# wifi_main_fix.net
KiCad netlist of a schematic drawn in EAGLE
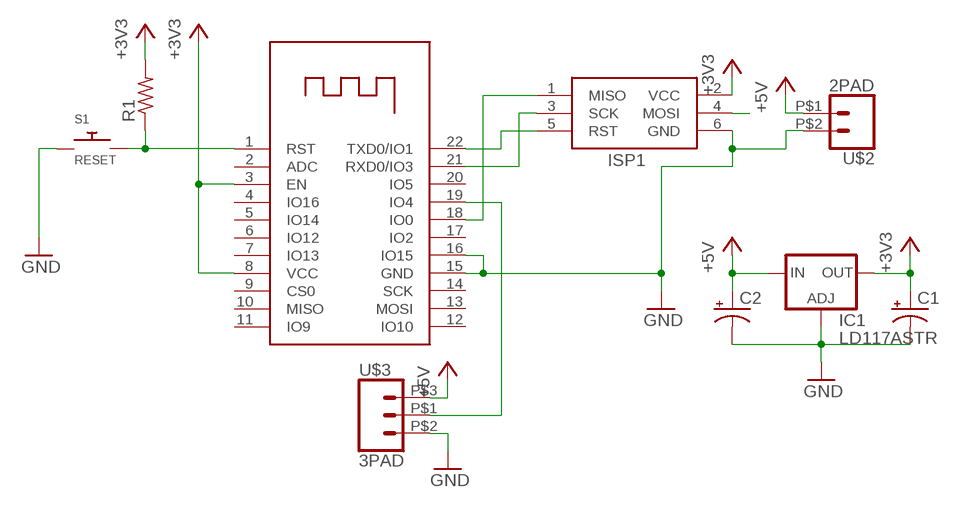
[diagram p0: schematic, sheet 1]

(export (version "E")
  (design (tool "Eeschema 10.0.6"))
  (components
    (comp (ref "C1")
      (value "CPOL-US153CLV-0405")
      (footprint "eagle-import:153CLV-0405")
      (libsource (lib "eagle-import") (part "CPOL-US153CLV-0405"))
    )
    (comp (ref "C2")
      (value "CPOL-US153CLV-0405")
      (footprint "eagle-import:153CLV-0405")
      (libsource (lib "eagle-import") (part "CPOL-US153CLV-0405"))
    )
    (comp (ref "IC1")
      (value "LD117ASTR")
      (footprint "eagle-import:SOT223")
      (libsource (lib "eagle-import") (part "LD117A?STR"))
    )
    (comp (ref "ISP1")
      (value "AVRISP-6")
      (footprint "eagle-import:AVRISP")
      (libsource (lib "eagle-import") (part "AVRISP-6"))
    )
    (comp (ref "R1")
      (value "R-US_R0805")
      (footprint "eagle-import:R0805")
      (libsource (lib "eagle-import") (part "R-US_R0805"))
    )
    (comp (ref "S1")
      (value "RESET")
      (footprint "eagle-import:B3F-1000")
      (libsource (lib "eagle-import") (part "BUTTON"))
    )
    (comp (ref "U$1")
      (value "ESP-12F")
      (footprint "eagle-import:ESP-12F")
      (libsource (lib "eagle-import") (part "ESP-12F"))
    )
    (comp (ref "U$2")
      (value "2PAD")
      (footprint "eagle-import:2PAD")
      (libsource (lib "eagle-import") (part "2PAD"))
    )
    (comp (ref "U$3")
      (value "3PAD")
      (footprint "eagle-import:3PAD")
      (libsource (lib "eagle-import") (part "3PAD"))
    )
  )
  (nets
    (net (code "1") (name "+3V3") (class "Default")
      (node (ref "C1") (pin "+") (pinfunction "+_+") (pintype "passive"))
      (node (ref "IC1") (pin "4") (pinfunction "OUT_4") (pintype "passive"))
      (node (ref "ISP1") (pin "2") (pinfunction "VCC_2") (pintype "power_in"))
      (node (ref "R1") (pin "2") (pinfunction "2_2") (pintype "passive"))
      (node (ref "U$1") (pin "3") (pinfunction "EN_3") (pintype "bidirectional"))
      (node (ref "U$1") (pin "8") (pinfunction "VCC_8") (pintype "bidirectional"))
    )
    (net (code "2") (name "+5V") (class "Default")
      (node (ref "C2") (pin "+") (pinfunction "+_+") (pintype "passive"))
      (node (ref "IC1") (pin "3") (pinfunction "IN_3") (pintype "input"))
      (node (ref "U$2") (pin "P$1") (pinfunction "1_P$1") (pintype "passive"))
      (node (ref "U$3") (pin "P$3") (pinfunction "3_P$3") (pintype "passive"))
    )
    (net (code "3") (name "GND") (class "Default")
      (node (ref "C1") (pin "-") (pinfunction "-_-") (pintype "passive"))
      (node (ref "C2") (pin "-") (pinfunction "-_-") (pintype "passive"))
      (node (ref "IC1") (pin "1") (pinfunction "ADJ_1") (pintype "input"))
      (node (ref "ISP1") (pin "6") (pinfunction "GND_6") (pintype "power_in"))
      (node (ref "S1") (pin "1") (pinfunction "P$1_1") (pintype "passive"))
      (node (ref "S1") (pin "2") (pinfunction "P$1_2") (pintype "passive"))
      (node (ref "U$1") (pin "15") (pinfunction "GND_15") (pintype "bidirectional"))
      (node (ref "U$1") (pin "16") (pinfunction "IO15_16") (pintype "bidirectional"))
      (node (ref "U$2") (pin "P$2") (pinfunction "2_P$2") (pintype "passive"))
      (node (ref "U$3") (pin "P$2") (pinfunction "1_P$2") (pintype "passive"))
    )
    (net (code "4") (name "Net-(ISP1-MISO)") (class "Default")
      (node (ref "ISP1") (pin "1") (pinfunction "MISO_1") (pintype "input"))
      (node (ref "U$1") (pin "18") (pinfunction "IO0_18") (pintype "bidirectional"))
    )
    (net (code "5") (name "Net-(ISP1-RST)") (class "Default")
      (node (ref "ISP1") (pin "5") (pinfunction "RST_5") (pintype "output"))
      (node (ref "U$1") (pin "22") (pinfunction "TXD0/IO1_22") (pintype "bidirectional"))
    )
    (net (code "6") (name "Net-(ISP1-SCK)") (class "Default")
      (node (ref "ISP1") (pin "3") (pinfunction "SCK_3") (pintype "output"))
      (node (ref "U$1") (pin "21") (pinfunction "RXD0/IO3_21") (pintype "bidirectional"))
    )
    (net (code "7") (name "Net-(U$1-IO4)") (class "Default")
      (node (ref "U$1") (pin "19") (pinfunction "IO4_19") (pintype "bidirectional"))
      (node (ref "U$3") (pin "P$1") (pinfunction "2_P$1") (pintype "passive"))
    )
    (net (code "8") (name "Net-(U$1-RST)") (class "Default")
      (node (ref "R1") (pin "1") (pinfunction "1_1") (pintype "passive"))
      (node (ref "S1") (pin "3") (pinfunction "P$2_3") (pintype "passive"))
      (node (ref "S1") (pin "4") (pinfunction "P$2_4") (pintype "passive"))
      (node (ref "U$1") (pin "1") (pinfunction "RST_1") (pintype "bidirectional"))
    )
    (net (code "9") (name "unconnected-(ISP1-MOSI-Pad4)") (class "Default")
      (node (ref "ISP1") (pin "4") (pinfunction "MOSI_4") (pintype "output"))
    )
    (net (code "10") (name "unconnected-(U$1-ADC-Pad2)") (class "Default")
      (node (ref "U$1") (pin "2") (pinfunction "ADC_2") (pintype "bidirectional"))
    )
    (net (code "11") (name "unconnected-(U$1-CS0-Pad9)") (class "Default")
      (node (ref "U$1") (pin "9") (pinfunction "CS0_9") (pintype "bidirectional"))
    )
    (net (code "12") (name "unconnected-(U$1-IO2-Pad17)") (class "Default")
      (node (ref "U$1") (pin "17") (pinfunction "IO2_17") (pintype "bidirectional"))
    )
    (net (code "13") (name "unconnected-(U$1-IO5-Pad20)") (class "Default")
      (node (ref "U$1") (pin "20") (pinfunction "IO5_20") (pintype "bidirectional"))
    )
    (net (code "14") (name "unconnected-(U$1-IO9-Pad11)") (class "Default")
      (node (ref "U$1") (pin "11") (pinfunction "IO9_11") (pintype "bidirectional"))
    )
    (net (code "15") (name "unconnected-(U$1-IO10-Pad12)") (class "Default")
      (node (ref "U$1") (pin "12") (pinfunction "IO10_12") (pintype "bidirectional"))
    )
    (net (code "16") (name "unconnected-(U$1-IO12-Pad6)") (class "Default")
      (node (ref "U$1") (pin "6") (pinfunction "IO12_6") (pintype "bidirectional"))
    )
    (net (code "17") (name "unconnected-(U$1-IO13-Pad7)") (class "Default")
      (node (ref "U$1") (pin "7") (pinfunction "IO13_7") (pintype "bidirectional"))
    )
    (net (code "18") (name "unconnected-(U$1-IO14-Pad5)") (class "Default")
      (node (ref "U$1") (pin "5") (pinfunction "IO14_5") (pintype "bidirectional"))
    )
    (net (code "19") (name "unconnected-(U$1-IO16-Pad4)") (class "Default")
      (node (ref "U$1") (pin "4") (pinfunction "IO16_4") (pintype "bidirectional"))
    )
    (net (code "20") (name "unconnected-(U$1-MISO-Pad10)") (class "Default")
      (node (ref "U$1") (pin "10") (pinfunction "MISO_10") (pintype "bidirectional"))
    )
    (net (code "21") (name "unconnected-(U$1-MOSI-Pad13)") (class "Default")
      (node (ref "U$1") (pin "13") (pinfunction "MOSI_13") (pintype "bidirectional"))
    )
    (net (code "22") (name "unconnected-(U$1-SCK-Pad14)") (class "Default")
      (node (ref "U$1") (pin "14") (pinfunction "SCK_14") (pintype "bidirectional"))
    )
  )
)
